# OpAmp-Inverting-3Transistor-alt2.net
KiCad netlist of a schematic drawn in EAGLE
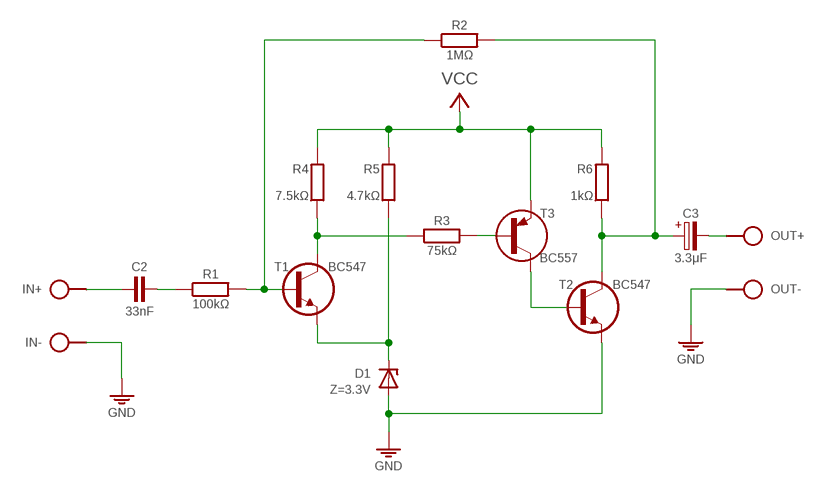
[diagram p0: schematic, sheet 1]

(export (version "E")
  (design (tool "Eeschema 10.0.6"))
  (components
    (comp (ref "C2")
      (value "33nF")
      (footprint "eagle-import:C050-020X044")
      (libsource (lib "eagle-import") (part "C050-020X044"))
    )
    (comp (ref "C3")
      (value "3.3μF")
      (footprint "eagle-import:E2.5-4_V")
      (libsource (lib "eagle-import") (part "CPOLE2,5-4/V"))
    )
    (comp (ref "D1")
      (value "Z=3.3V")
      (footprint "eagle-import:DO34Z2,5")
      (libsource (lib "eagle-import") (part "Z-DIODE34Z2,5"))
    )
    (comp (ref "IN")
      (value "SPAD+--+")
      (footprint "eagle-import:SPAD-+")
      (libsource (lib "eagle-import") (part "SPAD+--+"))
    )
    (comp (ref "J1")
      (value "VCC_GNDPWR-R")
      (footprint "eagle-import:PWR-R")
      (libsource (lib "eagle-import") (part "VCC_GNDPWR-R"))
    )
    (comp (ref "OUT")
      (value "SPAD+-+-")
      (footprint "eagle-import:SPAD+-")
      (libsource (lib "eagle-import") (part "SPAD+-+-"))
    )
    (comp (ref "R1")
      (value "100kΩ")
      (footprint "eagle-import:0204_10-V")
      (libsource (lib "eagle-import") (part "R-H0204/10-V"))
    )
    (comp (ref "R2")
      (value "1MΩ")
      (footprint "eagle-import:0204_10")
      (libsource (lib "eagle-import") (part "R-H0204/10"))
    )
    (comp (ref "R3")
      (value "75kΩ")
      (footprint "eagle-import:0204_10")
      (libsource (lib "eagle-import") (part "R-H0204/10"))
    )
    (comp (ref "R4")
      (value "7.5kΩ")
      (footprint "eagle-import:0204_10")
      (libsource (lib "eagle-import") (part "R0204/10"))
    )
    (comp (ref "R5")
      (value "4.7kΩ")
      (footprint "eagle-import:0204_10")
      (libsource (lib "eagle-import") (part "R0204/10"))
    )
    (comp (ref "R6")
      (value "1kΩ")
      (footprint "eagle-import:0204_10-V")
      (libsource (lib "eagle-import") (part "R0204/10-V"))
    )
    (comp (ref "T1")
      (value "BC547")
      (footprint "eagle-import:TO92-CBE")
      (libsource (lib "eagle-import") (part "BC547CBE"))
    )
    (comp (ref "T2")
      (value "BC547")
      (footprint "eagle-import:TO92-CBE")
      (libsource (lib "eagle-import") (part "BC547CBE"))
    )
    (comp (ref "T3")
      (value "BC557")
      (footprint "eagle-import:TO92-CBE")
      (libsource (lib "eagle-import") (part "BC557CBE"))
    )
  )
  (nets
    (net (code "1") (name "GND") (class "Default")
      (node (ref "D1") (pin "A") (pinfunction "A_A") (pintype "passive"))
      (node (ref "IN") (pin "1") (pinfunction "P$1_1") (pintype "passive"))
      (node (ref "J1") (pin "1") (pinfunction "GND_1") (pintype "power_in"))
      (node (ref "OUT") (pin "1") (pinfunction "P$1_1") (pintype "passive"))
      (node (ref "T2") (pin "E") (pinfunction "E_E") (pintype "passive"))
    )
    (net (code "2") (name "Net-(C2-Pad1)") (class "Default")
      (node (ref "C2") (pin "1") (pinfunction "1_1") (pintype "passive"))
      (node (ref "R1") (pin "1") (pinfunction "1_1") (pintype "passive"))
    )
    (net (code "3") (name "Net-(C3-Pad+)") (class "Default")
      (node (ref "C3") (pin "+") (pinfunction "+_+") (pintype "passive"))
      (node (ref "R2") (pin "2") (pinfunction "2_2") (pintype "passive"))
      (node (ref "R6") (pin "2") (pinfunction "2_2") (pintype "passive"))
      (node (ref "T2") (pin "C") (pinfunction "C_C") (pintype "passive"))
    )
    (net (code "4") (name "Net-(INA-P$1)") (class "Default")
      (node (ref "C2") (pin "2") (pinfunction "2_2") (pintype "passive"))
      (node (ref "IN") (pin "2") (pinfunction "P$1_2") (pintype "passive"))
    )
    (net (code "5") (name "Net-(J1A-VCC)") (class "Default")
      (node (ref "J1") (pin "2") (pinfunction "VCC_2") (pintype "power_in"))
      (node (ref "R4") (pin "2") (pinfunction "1_2") (pintype "passive"))
      (node (ref "R5") (pin "2") (pinfunction "1_2") (pintype "passive"))
      (node (ref "R6") (pin "1") (pinfunction "1_1") (pintype "passive"))
      (node (ref "T3") (pin "E") (pinfunction "E_E") (pintype "passive"))
    )
    (net (code "6") (name "Net-(OUTA-P$1)") (class "Default")
      (node (ref "C3") (pin "-") (pinfunction "-_-") (pintype "passive"))
      (node (ref "OUT") (pin "2") (pinfunction "P$1_2") (pintype "passive"))
    )
    (net (code "7") (name "Net-(R1-Pad2)") (class "Default")
      (node (ref "R1") (pin "2") (pinfunction "2_2") (pintype "passive"))
      (node (ref "R2") (pin "1") (pinfunction "1_1") (pintype "passive"))
      (node (ref "T1") (pin "B") (pinfunction "B_B") (pintype "passive"))
    )
    (net (code "8") (name "Net-(R3-Pad2)") (class "Default")
      (node (ref "R3") (pin "2") (pinfunction "2_2") (pintype "passive"))
      (node (ref "T3") (pin "B") (pinfunction "B_B") (pintype "passive"))
    )
    (net (code "9") (name "Net-(R4-2)") (class "Default")
      (node (ref "R3") (pin "1") (pinfunction "1_1") (pintype "passive"))
      (node (ref "R4") (pin "1") (pinfunction "2_1") (pintype "passive"))
      (node (ref "T1") (pin "C") (pinfunction "C_C") (pintype "passive"))
    )
    (net (code "10") (name "Net-(R5-2)") (class "Default")
      (node (ref "D1") (pin "C") (pinfunction "C_C") (pintype "passive"))
      (node (ref "R5") (pin "1") (pinfunction "2_1") (pintype "passive"))
      (node (ref "T1") (pin "E") (pinfunction "E_E") (pintype "passive"))
    )
    (net (code "11") (name "Net-(T2-PadB)") (class "Default")
      (node (ref "T2") (pin "B") (pinfunction "B_B") (pintype "passive"))
      (node (ref "T3") (pin "C") (pinfunction "C_C") (pintype "passive"))
    )
  )
)
